# blinkm_mk2r.net
KiCad netlist of a schematic drawn in EAGLE
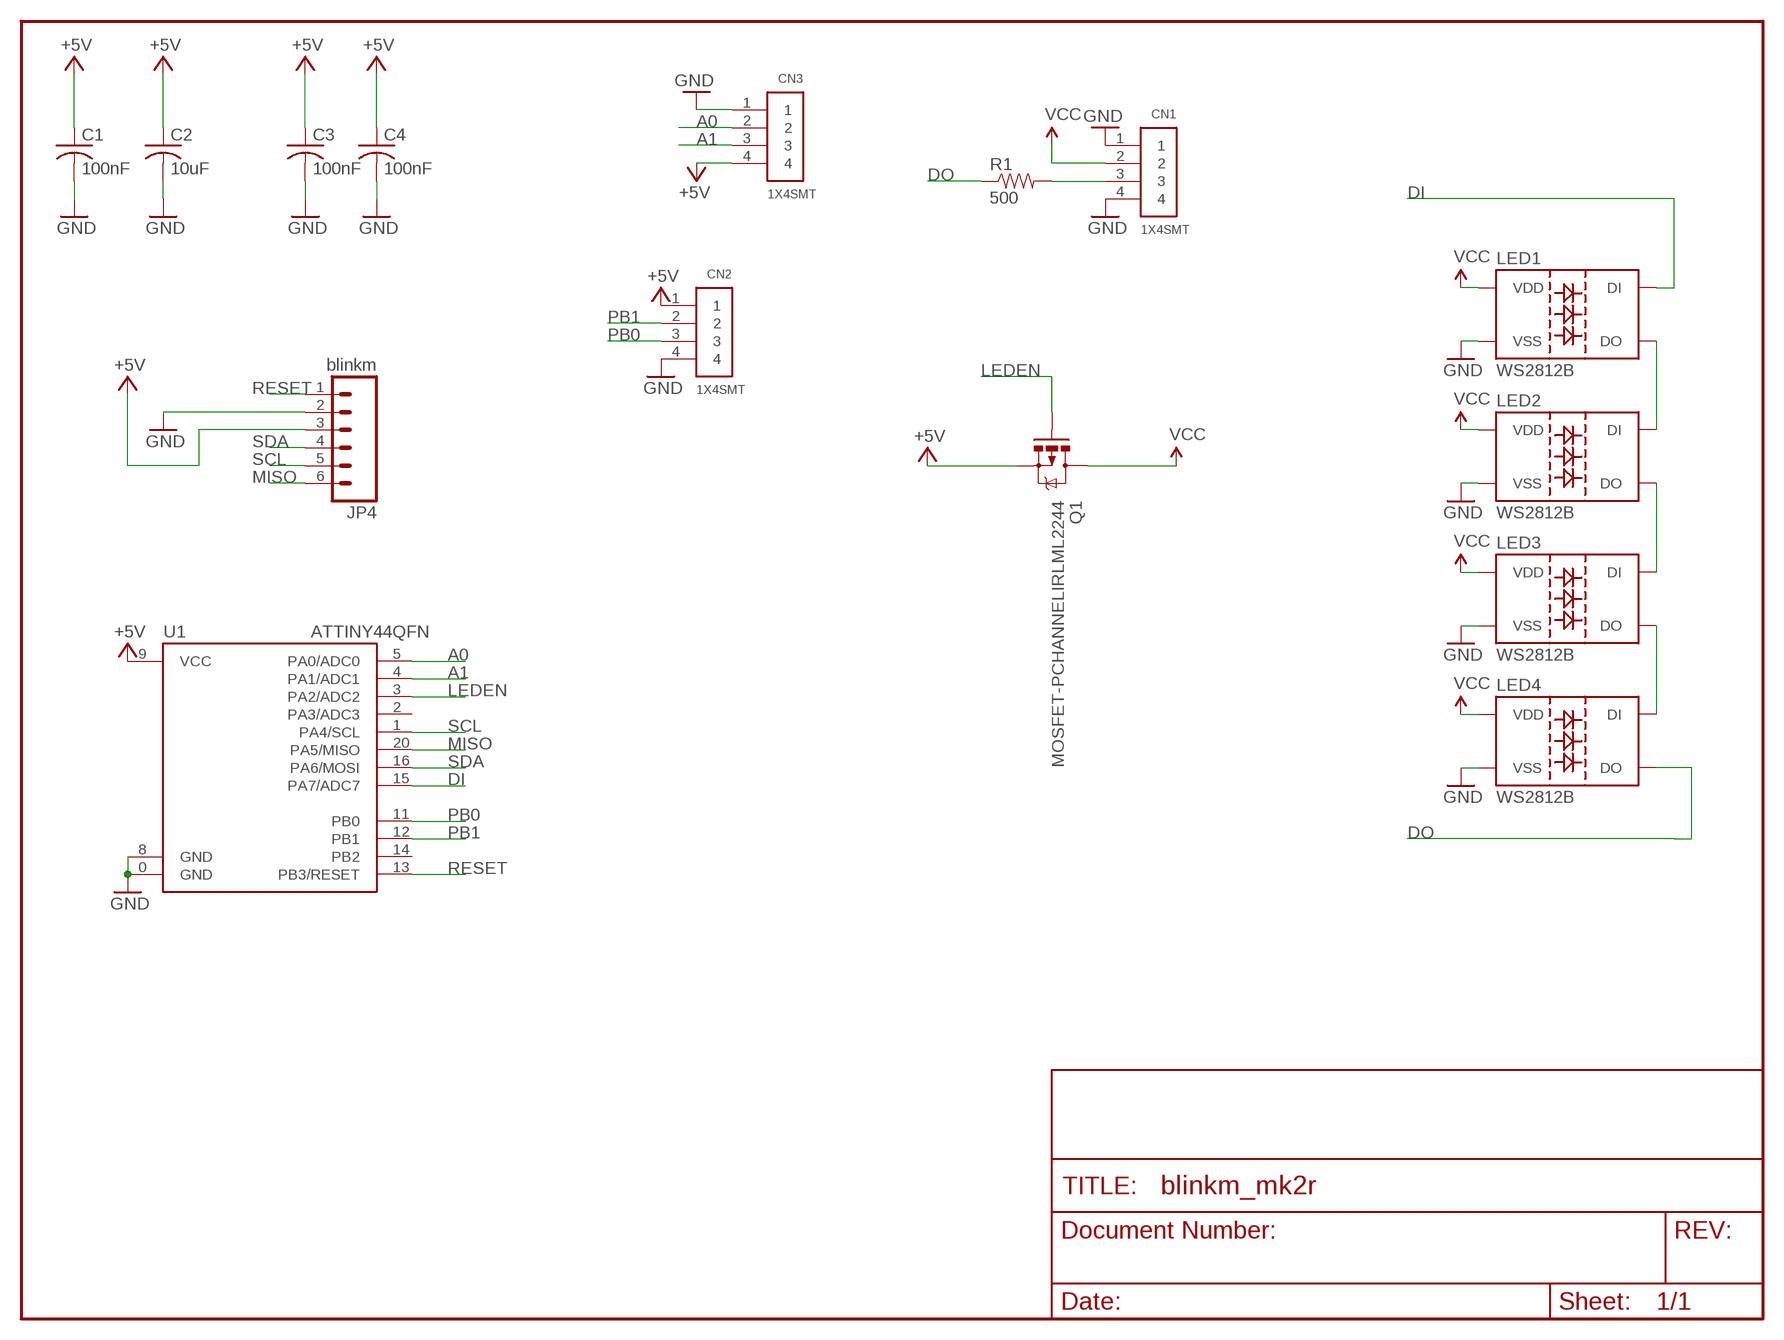
[diagram p0: schematic, sheet 1]

(export (version "E")
  (design (tool "Eeschema 10.0.6"))
  (components
    (comp (ref "C1")
      (value "100nF")
      (footprint "eagle-import:C0603")
      (libsource (lib "eagle-import") (part "C-USC0603"))
    )
    (comp (ref "C2")
      (value "10uF")
      (footprint "eagle-import:C0603")
      (libsource (lib "eagle-import") (part "C-USC0603"))
    )
    (comp (ref "C3")
      (value "100nF")
      (footprint "eagle-import:C0603")
      (libsource (lib "eagle-import") (part "C-USC0603"))
    )
    (comp (ref "C4")
      (value "100nF")
      (footprint "eagle-import:C0603")
      (libsource (lib "eagle-import") (part "C-USC0603"))
    )
    (comp (ref "CN1")
      (value "1X4SMT")
      (footprint "eagle-import:1X4-SMT")
      (libsource (lib "eagle-import") (part "1X4SMT"))
    )
    (comp (ref "CN2")
      (value "1X4SMT")
      (footprint "eagle-import:1X4-SMT")
      (libsource (lib "eagle-import") (part "1X4SMT"))
    )
    (comp (ref "CN3")
      (value "1X4SMT")
      (footprint "eagle-import:1X4-SMT")
      (libsource (lib "eagle-import") (part "1X4SMT"))
    )
    (comp (ref "JP4")
      (value "blinkm")
      (footprint "eagle-import:1X06_LOCK")
      (libsource (lib "eagle-import") (part "M06LOCK"))
    )
    (comp (ref "LED1")
      (value "WS2812B")
      (footprint "eagle-import:WS2812B")
      (libsource (lib "eagle-import") (part "WS2812B"))
    )
    (comp (ref "LED2")
      (value "WS2812B")
      (footprint "eagle-import:WS2812B")
      (libsource (lib "eagle-import") (part "WS2812B"))
    )
    (comp (ref "LED3")
      (value "WS2812B")
      (footprint "eagle-import:WS2812B")
      (libsource (lib "eagle-import") (part "WS2812B"))
    )
    (comp (ref "LED4")
      (value "WS2812B")
      (footprint "eagle-import:WS2812B")
      (libsource (lib "eagle-import") (part "WS2812B"))
    )
    (comp (ref "Q1")
      (value "MOSFET-PCHANNELIRLML2244")
      (footprint "eagle-import:SOT23-3")
      (libsource (lib "eagle-import") (part "MOSFET-PCHANNELIRLML2244"))
    )
    (comp (ref "R1")
      (value "500")
      (footprint "eagle-import:0603-RES")
      (libsource (lib "eagle-import") (part "RESISTOR0603"))
    )
    (comp (ref "U1")
      (value "ATTINY44QFN")
      (footprint "eagle-import:QFN20")
      (libsource (lib "eagle-import") (part "ATTINY24QFN"))
    )
  )
  (nets
    (net (code "1") (name "+5V") (class "Default")
      (node (ref "C1") (pin "1") (pinfunction "1_1") (pintype "passive"))
      (node (ref "C2") (pin "1") (pinfunction "1_1") (pintype "passive"))
      (node (ref "C3") (pin "1") (pinfunction "1_1") (pintype "passive"))
      (node (ref "C4") (pin "1") (pinfunction "1_1") (pintype "passive"))
      (node (ref "CN2") (pin "1") (pinfunction "1_1") (pintype "bidirectional"))
      (node (ref "CN3") (pin "4") (pinfunction "4_4") (pintype "bidirectional"))
      (node (ref "JP4") (pin "3") (pinfunction "3_3") (pintype "passive"))
      (node (ref "Q1") (pin "2") (pinfunction "S_2") (pintype "passive"))
      (node (ref "U1") (pin "9") (pinfunction "VCC_9") (pintype "bidirectional"))
    )
    (net (code "2") (name "/A0") (class "Default")
      (node (ref "CN3") (pin "2") (pinfunction "2_2") (pintype "bidirectional"))
      (node (ref "U1") (pin "5") (pinfunction "PA0/ADC0_5") (pintype "bidirectional"))
    )
    (net (code "3") (name "/A1") (class "Default")
      (node (ref "CN3") (pin "3") (pinfunction "3_3") (pintype "bidirectional"))
      (node (ref "U1") (pin "4") (pinfunction "PA1/ADC1_4") (pintype "bidirectional"))
    )
    (net (code "4") (name "/DI") (class "Default")
      (node (ref "LED1") (pin "4") (pinfunction "DI_4") (pintype "bidirectional"))
      (node (ref "U1") (pin "15") (pinfunction "PA7/ADC7_15") (pintype "bidirectional"))
    )
    (net (code "5") (name "/DO") (class "Default")
      (node (ref "LED4") (pin "2") (pinfunction "DO_2") (pintype "bidirectional"))
      (node (ref "R1") (pin "1") (pinfunction "1_1") (pintype "passive"))
    )
    (net (code "6") (name "/LEDEN") (class "Default")
      (node (ref "Q1") (pin "1") (pinfunction "G_1") (pintype "passive"))
      (node (ref "U1") (pin "3") (pinfunction "PA2/ADC2_3") (pintype "bidirectional"))
    )
    (net (code "7") (name "/MISO") (class "Default")
      (node (ref "JP4") (pin "6") (pinfunction "6_6") (pintype "passive"))
      (node (ref "U1") (pin "20") (pinfunction "PA5/MISO_20") (pintype "bidirectional"))
    )
    (net (code "8") (name "/PB0") (class "Default")
      (node (ref "CN2") (pin "3") (pinfunction "3_3") (pintype "bidirectional"))
      (node (ref "U1") (pin "11") (pinfunction "PB0_11") (pintype "bidirectional"))
    )
    (net (code "9") (name "/PB1") (class "Default")
      (node (ref "CN2") (pin "2") (pinfunction "2_2") (pintype "bidirectional"))
      (node (ref "U1") (pin "12") (pinfunction "PB1_12") (pintype "bidirectional"))
    )
    (net (code "10") (name "/RESET") (class "Default")
      (node (ref "JP4") (pin "1") (pinfunction "1_1") (pintype "passive"))
      (node (ref "U1") (pin "13") (pinfunction "PB3/RESET_13") (pintype "bidirectional"))
    )
    (net (code "11") (name "/SCL") (class "Default")
      (node (ref "JP4") (pin "5") (pinfunction "5_5") (pintype "passive"))
      (node (ref "U1") (pin "1") (pinfunction "PA4/SCL_1") (pintype "bidirectional"))
    )
    (net (code "12") (name "/SDA") (class "Default")
      (node (ref "JP4") (pin "4") (pinfunction "4_4") (pintype "passive"))
      (node (ref "U1") (pin "16") (pinfunction "PA6/MOSI_16") (pintype "bidirectional"))
    )
    (net (code "13") (name "GND") (class "Default")
      (node (ref "C1") (pin "2") (pinfunction "2_2") (pintype "passive"))
      (node (ref "C2") (pin "2") (pinfunction "2_2") (pintype "passive"))
      (node (ref "C3") (pin "2") (pinfunction "2_2") (pintype "passive"))
      (node (ref "C4") (pin "2") (pinfunction "2_2") (pintype "passive"))
      (node (ref "CN1") (pin "1") (pinfunction "1_1") (pintype "bidirectional"))
      (node (ref "CN1") (pin "4") (pinfunction "4_4") (pintype "bidirectional"))
      (node (ref "CN2") (pin "4") (pinfunction "4_4") (pintype "bidirectional"))
      (node (ref "CN3") (pin "1") (pinfunction "1_1") (pintype "bidirectional"))
      (node (ref "JP4") (pin "2") (pinfunction "2_2") (pintype "passive"))
      (node (ref "LED1") (pin "3") (pinfunction "VSS_3") (pintype "bidirectional"))
      (node (ref "LED2") (pin "3") (pinfunction "VSS_3") (pintype "bidirectional"))
      (node (ref "LED3") (pin "3") (pinfunction "VSS_3") (pintype "bidirectional"))
      (node (ref "LED4") (pin "3") (pinfunction "VSS_3") (pintype "bidirectional"))
      (node (ref "U1") (pin "0") (pinfunction "GND_0") (pintype "bidirectional"))
      (node (ref "U1") (pin "8") (pinfunction "GND_8") (pintype "bidirectional"))
    )
    (net (code "14") (name "Net-(CN1-Pad3)") (class "Default")
      (node (ref "CN1") (pin "3") (pinfunction "3_3") (pintype "bidirectional"))
      (node (ref "R1") (pin "2") (pinfunction "2_2") (pintype "passive"))
    )
    (net (code "15") (name "Net-(LED1-DO)") (class "Default")
      (node (ref "LED1") (pin "2") (pinfunction "DO_2") (pintype "bidirectional"))
      (node (ref "LED2") (pin "4") (pinfunction "DI_4") (pintype "bidirectional"))
    )
    (net (code "16") (name "Net-(LED2-DO)") (class "Default")
      (node (ref "LED2") (pin "2") (pinfunction "DO_2") (pintype "bidirectional"))
      (node (ref "LED3") (pin "4") (pinfunction "DI_4") (pintype "bidirectional"))
    )
    (net (code "17") (name "Net-(LED3-DO)") (class "Default")
      (node (ref "LED3") (pin "2") (pinfunction "DO_2") (pintype "bidirectional"))
      (node (ref "LED4") (pin "4") (pinfunction "DI_4") (pintype "bidirectional"))
    )
    (net (code "18") (name "VCC") (class "Default")
      (node (ref "CN1") (pin "2") (pinfunction "2_2") (pintype "bidirectional"))
      (node (ref "LED1") (pin "1") (pinfunction "VDD_1") (pintype "bidirectional"))
      (node (ref "LED2") (pin "1") (pinfunction "VDD_1") (pintype "bidirectional"))
      (node (ref "LED3") (pin "1") (pinfunction "VDD_1") (pintype "bidirectional"))
      (node (ref "LED4") (pin "1") (pinfunction "VDD_1") (pintype "bidirectional"))
      (node (ref "Q1") (pin "3") (pinfunction "D_3") (pintype "passive"))
    )
    (net (code "19") (name "unconnected-(U1-PA3{slash}ADC3-Pad2)") (class "Default")
      (node (ref "U1") (pin "2") (pinfunction "PA3/ADC3_2") (pintype "bidirectional"))
    )
    (net (code "20") (name "unconnected-(U1-PB2-Pad14)") (class "Default")
      (node (ref "U1") (pin "14") (pinfunction "PB2_14") (pintype "bidirectional"))
    )
  )
)
